# board.net
KiCad netlist of a schematic drawn in EAGLE
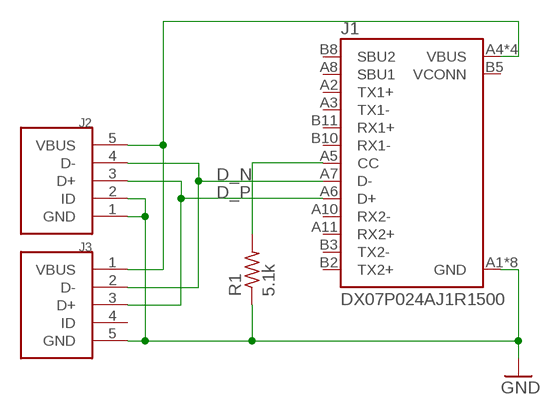
[diagram p0: schematic, sheet 1]

(export (version "E")
  (design (tool "Eeschema 10.0.6"))
  (components
    (comp (ref "J1")
      (value "DX07P024AJ1R1500")
      (footprint "eagle-import:JAE_DX07P024AJ1R1500")
      (fields (field (name "DIGI-KEY_PART_NUMBER") "670-2868-1-ND") (field (name "MF") "JAE Electronics"))
      (libsource (lib "eagle-import") (part "DX07P024AJ1R1500"))
    )
    (comp (ref "J2")
      (value "USB59453-051110EDHLF")
      (footprint "eagle-import:59453-051110EDHLF")
      (libsource (lib "eagle-import") (part "USB59453-051110EDHLF"))
    )
    (comp (ref "J3")
      (value "USBSEEK-USB")
      (footprint "eagle-import:SEEK-USB")
      (libsource (lib "eagle-import") (part "USBSEEK-USB"))
    )
    (comp (ref "R1")
      (value "5.1k")
      (footprint "eagle-import:R0402")
      (libsource (lib "eagle-import") (part "R-US_R0402"))
    )
  )
  (nets
    (net (code "1") (name "/D_N") (class "Default")
      (node (ref "J1") (pin "A7") (pinfunction "D-_A7") (pintype "bidirectional"))
      (node (ref "J2") (pin "4") (pinfunction "D-_4") (pintype "bidirectional"))
      (node (ref "J3") (pin "2") (pinfunction "D-_2") (pintype "bidirectional"))
    )
    (net (code "2") (name "/D_P") (class "Default")
      (node (ref "J1") (pin "A6") (pinfunction "D+_A6") (pintype "bidirectional"))
      (node (ref "J2") (pin "3") (pinfunction "D+_3") (pintype "bidirectional"))
      (node (ref "J3") (pin "3") (pinfunction "D+_3") (pintype "bidirectional"))
    )
    (net (code "3") (name "/VCONN") (class "Default")
      (node (ref "J1") (pin "B5") (pinfunction "VCONN_B5") (pintype "power_in"))
    )
    (net (code "4") (name "GND") (class "Default")
      (node (ref "J1") (pin "A1") (pinfunction "GND_A1") (pintype "power_in"))
      (node (ref "J1") (pin "A12") (pinfunction "GND_A12") (pintype "power_in"))
      (node (ref "J1") (pin "B0") (pinfunction "GND_B0") (pintype "power_in"))
      (node (ref "J1") (pin "B1") (pinfunction "GND_B1") (pintype "power_in"))
      (node (ref "J1") (pin "B12") (pinfunction "GND_B12") (pintype "power_in"))
      (node (ref "J1") (pin "B13") (pinfunction "GND_B13") (pintype "power_in"))
      (node (ref "J1") (pin "B17") (pinfunction "GND_B17") (pintype "power_in"))
      (node (ref "J1") (pin "B18") (pinfunction "GND_B18") (pintype "power_in"))
      (node (ref "J2") (pin "1") (pinfunction "GND_1") (pintype "power_in"))
      (node (ref "J2") (pin "2") (pinfunction "ID_2") (pintype "bidirectional"))
      (node (ref "J3") (pin "5") (pinfunction "GND_5") (pintype "power_in"))
      (node (ref "R1") (pin "1") (pinfunction "1_1") (pintype "passive"))
    )
    (net (code "5") (name "Net-(J1-CC)") (class "Default")
      (node (ref "J1") (pin "A5") (pinfunction "CC_A5") (pintype "bidirectional"))
      (node (ref "R1") (pin "2") (pinfunction "2_2") (pintype "passive"))
    )
    (net (code "6") (name "Net-(J2-VBUS)") (class "Default")
      (node (ref "J1") (pin "A4") (pinfunction "VBUS_A4") (pintype "power_in"))
      (node (ref "J1") (pin "A9") (pinfunction "VBUS_A9") (pintype "power_in"))
      (node (ref "J1") (pin "B4") (pinfunction "VBUS_B4") (pintype "power_in"))
      (node (ref "J1") (pin "B9") (pinfunction "VBUS_B9") (pintype "power_in"))
      (node (ref "J2") (pin "5") (pinfunction "VBUS_5") (pintype "power_in"))
      (node (ref "J3") (pin "1") (pinfunction "VBUS_1") (pintype "power_in"))
    )
    (net (code "7") (name "unconnected-(J1-RX1+-PadB11)") (class "Default")
      (node (ref "J1") (pin "B11") (pinfunction "RX1+_B11") (pintype "bidirectional"))
    )
    (net (code "8") (name "unconnected-(J1-RX1--PadB10)") (class "Default")
      (node (ref "J1") (pin "B10") (pinfunction "RX1-_B10") (pintype "bidirectional"))
    )
    (net (code "9") (name "unconnected-(J1-RX2+-PadA11)") (class "Default")
      (node (ref "J1") (pin "A11") (pinfunction "RX2+_A11") (pintype "bidirectional"))
    )
    (net (code "10") (name "unconnected-(J1-RX2--PadA10)") (class "Default")
      (node (ref "J1") (pin "A10") (pinfunction "RX2-_A10") (pintype "bidirectional"))
    )
    (net (code "11") (name "unconnected-(J1-SBU1-PadA8)") (class "Default")
      (node (ref "J1") (pin "A8") (pinfunction "SBU1_A8") (pintype "bidirectional"))
    )
    (net (code "12") (name "unconnected-(J1-SBU2-PadB8)") (class "Default")
      (node (ref "J1") (pin "B8") (pinfunction "SBU2_B8") (pintype "bidirectional"))
    )
    (net (code "13") (name "unconnected-(J1-TX1+-PadA2)") (class "Default")
      (node (ref "J1") (pin "A2") (pinfunction "TX1+_A2") (pintype "bidirectional"))
    )
    (net (code "14") (name "unconnected-(J1-TX1--PadA3)") (class "Default")
      (node (ref "J1") (pin "A3") (pinfunction "TX1-_A3") (pintype "bidirectional"))
    )
    (net (code "15") (name "unconnected-(J1-TX2+-PadB2)") (class "Default")
      (node (ref "J1") (pin "B2") (pinfunction "TX2+_B2") (pintype "bidirectional"))
    )
    (net (code "16") (name "unconnected-(J1-TX2--PadB3)") (class "Default")
      (node (ref "J1") (pin "B3") (pinfunction "TX2-_B3") (pintype "bidirectional"))
    )
    (net (code "17") (name "unconnected-(J3-ID-Pad4)") (class "Default")
      (node (ref "J3") (pin "4") (pinfunction "ID_4") (pintype "bidirectional"))
    )
  )
)
